# Arduino-on-breadboard.net
KiCad netlist of a schematic drawn in EAGLE
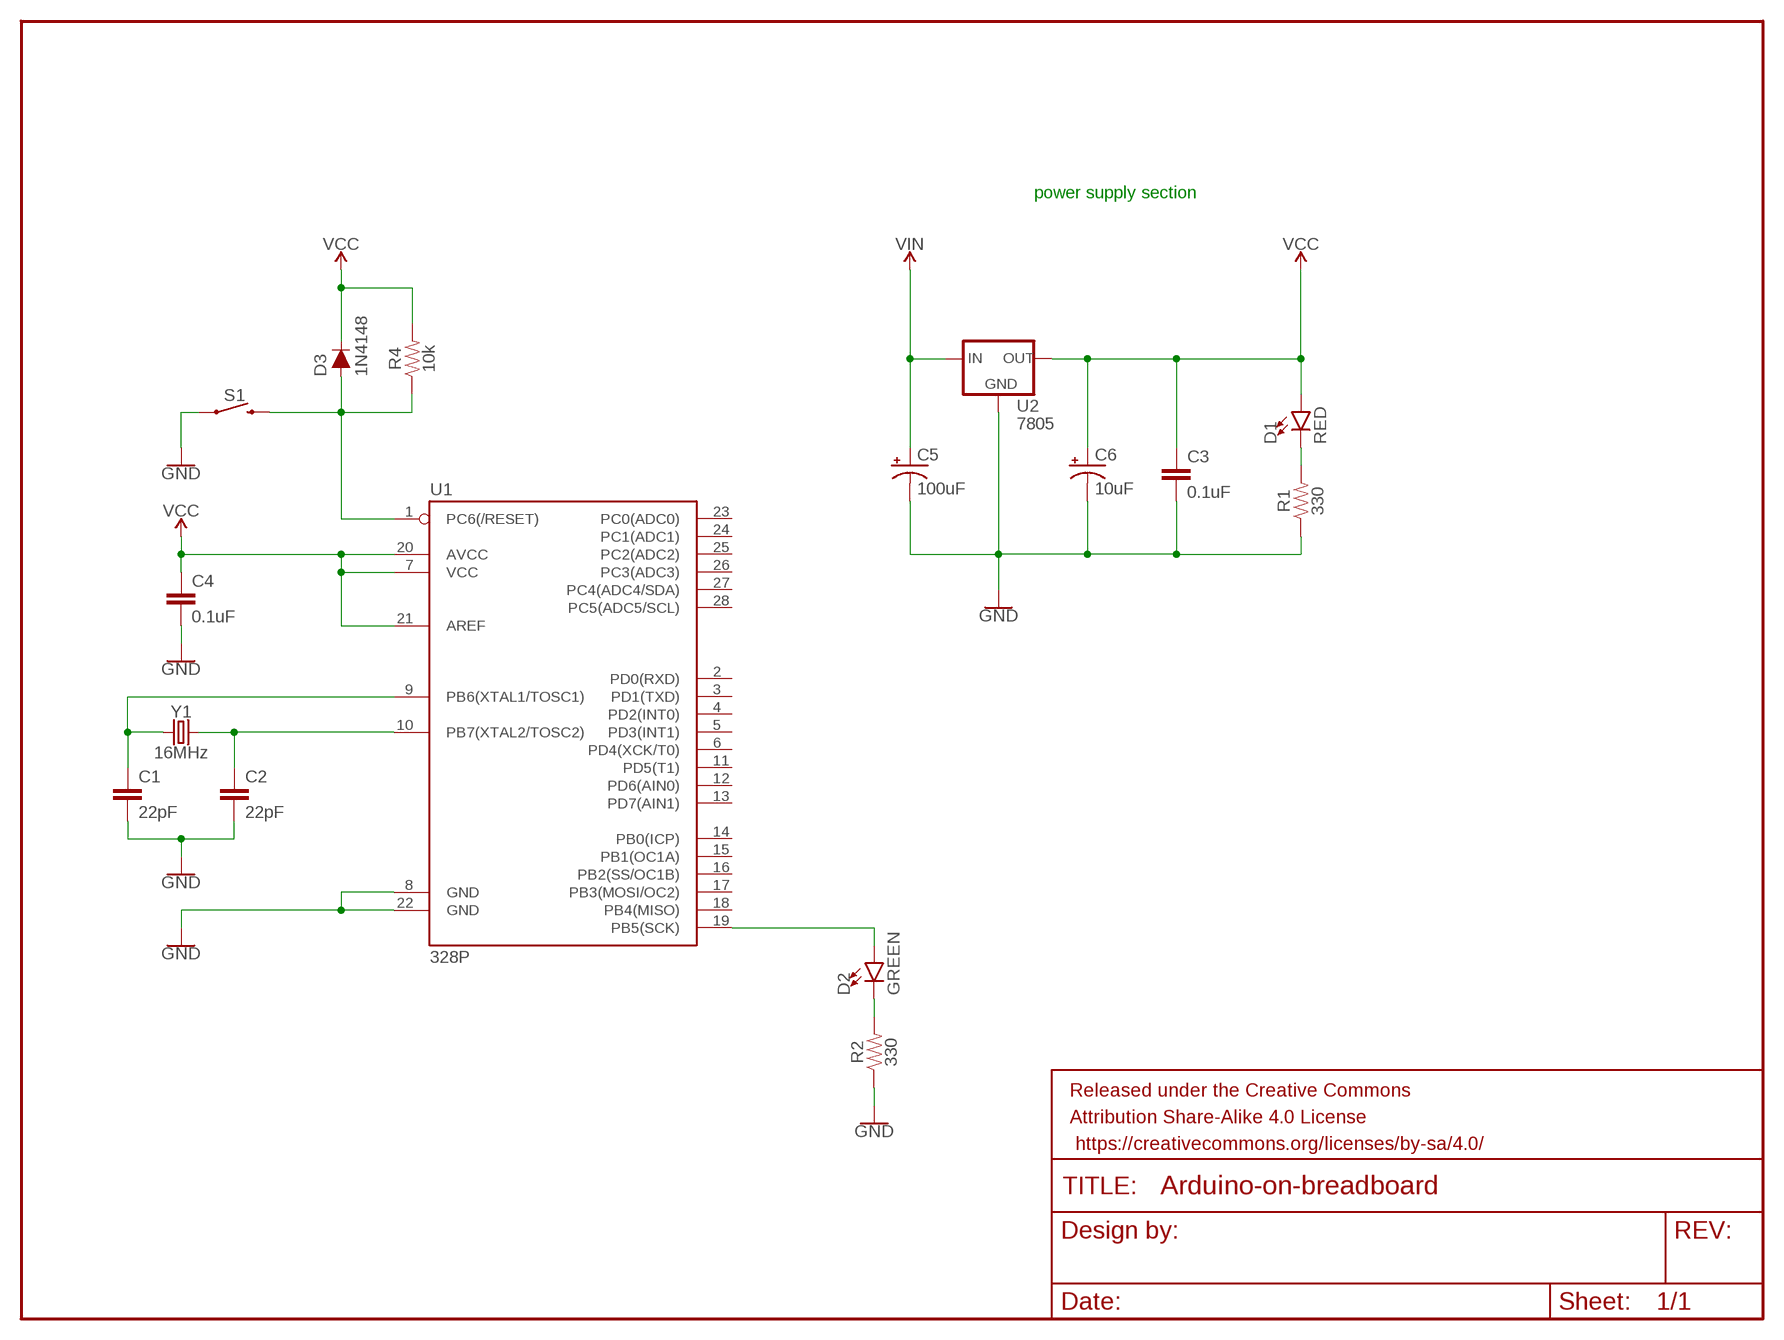
[diagram p0: schematic, sheet 1]

(export (version "E")
  (design (tool "Eeschema 10.0.6"))
  (components
    (comp (ref "C1")
      (value "22pF")
      (footprint "eagle-import:CAP-PTH-2.54")
      (libsource (lib "eagle-import") (part "22PF-PTH-2.54MM-200V-5%"))
    )
    (comp (ref "C2")
      (value "22pF")
      (footprint "eagle-import:CAP-PTH-2.54")
      (libsource (lib "eagle-import") (part "22PF-PTH-2.54MM-200V-5%"))
    )
    (comp (ref "C3")
      (value "0.1uF")
      (footprint "eagle-import:CAP-PTH-SMALL-KIT")
      (libsource (lib "eagle-import") (part "0.1UF-KIT-EZ-50V-20%"))
    )
    (comp (ref "C4")
      (value "0.1uF")
      (footprint "eagle-import:CAP-PTH-SMALL-KIT")
      (libsource (lib "eagle-import") (part "0.1UF-KIT-EZ-50V-20%"))
    )
    (comp (ref "C5")
      (value "100uF")
      (footprint "eagle-import:CPOL-RADIAL-2.5MM-6.5MM")
      (libsource (lib "eagle-import") (part "100UF-POLAR-RADIAL-2.5MM-25V-20%"))
    )
    (comp (ref "C6")
      (value "10uF")
      (footprint "eagle-import:CPOL-RADIAL-2.5MM-6.5MM")
      (libsource (lib "eagle-import") (part "100UF-POLAR-RADIAL-2.5MM-25V-20%"))
    )
    (comp (ref "D1")
      (value "RED")
      (footprint "eagle-import:LED_5MM")
      (libsource (lib "eagle-import") (part "LED5MM"))
    )
    (comp (ref "D2")
      (value "GREEN")
      (footprint "eagle-import:LED_5MM")
      (libsource (lib "eagle-import") (part "LED5MM"))
    )
    (comp (ref "D3")
      (value "1N4148")
      (footprint "eagle-import:DIODE-1N4148")
      (libsource (lib "eagle-import") (part "DIODE-1N4148"))
    )
    (comp (ref "FRAME1")
      (value "FRAME-LETTER")
      (footprint "eagle-import:CREATIVE_COMMONS")
      (libsource (lib "eagle-import") (part "FRAME-LETTER"))
    )
    (comp (ref "R1")
      (value "330")
      (footprint "eagle-import:AXIAL-0.3")
      (libsource (lib "eagle-import") (part "1KOHM-HORIZ-1/4W-5%"))
    )
    (comp (ref "R2")
      (value "330")
      (footprint "eagle-import:AXIAL-0.3")
      (libsource (lib "eagle-import") (part "1KOHM-HORIZ-1/4W-5%"))
    )
    (comp (ref "R4")
      (value "10k")
      (footprint "eagle-import:AXIAL-0.3")
      (libsource (lib "eagle-import") (part "1KOHM-HORIZ-1/4W-5%"))
    )
    (comp (ref "S1")
      (value "MOMENTARY-SWITCH-SPST-SMD-6.0X3.5MM")
      (footprint "eagle-import:TACTILE_SWITCH_SMD_6.0X3.5MM")
      (libsource (lib "eagle-import") (part "MOMENTARY-SWITCH-SPST-SMD-6.0X3.5MM"))
    )
    (comp (ref "U1")
      (value "328P")
      (footprint "eagle-import:DIP28")
      (libsource (lib "eagle-import") (part "ATMEGA328P_PDIP"))
    )
    (comp (ref "U2")
      (value "7805")
      (footprint "eagle-import:78XXL")
      (libsource (lib "eagle-import") (part "V_REG_78XXSIDE"))
    )
    (comp (ref "Y1")
      (value "16MHz")
      (footprint "eagle-import:HC49US")
      (libsource (lib "eagle-import") (part "CRYSTAL-16MHZPTH-HC49US"))
    )
  )
  (nets
    (net (code "1") (name "GND") (class "Default")
      (node (ref "C1") (pin "2") (pinfunction "2_2") (pintype "passive"))
      (node (ref "C2") (pin "2") (pinfunction "2_2") (pintype "passive"))
      (node (ref "C3") (pin "2") (pinfunction "2_2") (pintype "passive"))
      (node (ref "C4") (pin "2") (pinfunction "2_2") (pintype "passive"))
      (node (ref "C5") (pin "2") (pinfunction "-_2") (pintype "passive"))
      (node (ref "C6") (pin "2") (pinfunction "-_2") (pintype "passive"))
      (node (ref "R1") (pin "P$1") (pinfunction "1_P$1") (pintype "passive"))
      (node (ref "R2") (pin "P$1") (pinfunction "1_P$1") (pintype "passive"))
      (node (ref "S1") (pin "1") (pinfunction "1_1") (pintype "passive"))
      (node (ref "U1") (pin "22") (pinfunction "GND_22") (pintype "bidirectional"))
      (node (ref "U1") (pin "8") (pinfunction "GND_8") (pintype "bidirectional"))
      (node (ref "U2") (pin "GND") (pinfunction "GND_GND") (pintype "input"))
    )
    (net (code "2") (name "Net-(D1-C)") (class "Default")
      (node (ref "D1") (pin "K") (pinfunction "C_K") (pintype "passive"))
      (node (ref "R1") (pin "P$2") (pinfunction "2_P$2") (pintype "passive"))
    )
    (net (code "3") (name "Net-(D2-C)") (class "Default")
      (node (ref "D2") (pin "K") (pinfunction "C_K") (pintype "passive"))
      (node (ref "R2") (pin "P$2") (pinfunction "2_P$2") (pintype "passive"))
    )
    (net (code "4") (name "Net-(R4-1)") (class "Default")
      (node (ref "D3") (pin "A") (pinfunction "A_A") (pintype "passive"))
      (node (ref "R4") (pin "P$1") (pinfunction "1_P$1") (pintype "passive"))
      (node (ref "S1") (pin "2") (pinfunction "2_2") (pintype "passive"))
      (node (ref "U1") (pin "1") (pinfunction "PC6(/RESET)_1") (pintype "bidirectional"))
    )
    (net (code "5") (name "Net-(U1-PB5(SCK))") (class "Default")
      (node (ref "D2") (pin "A") (pinfunction "A_A") (pintype "passive"))
      (node (ref "U1") (pin "19") (pinfunction "PB5(SCK)_19") (pintype "bidirectional"))
    )
    (net (code "6") (name "Net-(U1-PB6(XTAL1{slash}TOSC1))") (class "Default")
      (node (ref "C1") (pin "1") (pinfunction "1_1") (pintype "passive"))
      (node (ref "U1") (pin "9") (pinfunction "PB6(XTAL1/TOSC1)_9") (pintype "bidirectional"))
      (node (ref "Y1") (pin "1") (pinfunction "1_1") (pintype "passive"))
    )
    (net (code "7") (name "Net-(U1-PB7(XTAL2{slash}TOSC2))") (class "Default")
      (node (ref "C2") (pin "1") (pinfunction "1_1") (pintype "passive"))
      (node (ref "U1") (pin "10") (pinfunction "PB7(XTAL2/TOSC2)_10") (pintype "bidirectional"))
      (node (ref "Y1") (pin "2") (pinfunction "2_2") (pintype "passive"))
    )
    (net (code "8") (name "VCC") (class "Default")
      (node (ref "C3") (pin "1") (pinfunction "1_1") (pintype "passive"))
      (node (ref "C4") (pin "1") (pinfunction "1_1") (pintype "passive"))
      (node (ref "C5") (pin "1") (pinfunction "+_1") (pintype "passive"))
      (node (ref "C6") (pin "1") (pinfunction "+_1") (pintype "passive"))
      (node (ref "D1") (pin "A") (pinfunction "A_A") (pintype "passive"))
      (node (ref "D3") (pin "C") (pinfunction "C_C") (pintype "passive"))
      (node (ref "R4") (pin "P$2") (pinfunction "2_P$2") (pintype "passive"))
      (node (ref "U1") (pin "20") (pinfunction "AVCC_20") (pintype "bidirectional"))
      (node (ref "U1") (pin "21") (pinfunction "AREF_21") (pintype "bidirectional"))
      (node (ref "U1") (pin "7") (pinfunction "VCC_7") (pintype "bidirectional"))
      (node (ref "U2") (pin "IN") (pinfunction "IN_IN") (pintype "input"))
      (node (ref "U2") (pin "OUT") (pinfunction "OUT_OUT") (pintype "passive"))
    )
    (net (code "9") (name "unconnected-(U1-PB0(ICP)-Pad14)") (class "Default")
      (node (ref "U1") (pin "14") (pinfunction "PB0(ICP)_14") (pintype "bidirectional"))
    )
    (net (code "10") (name "unconnected-(U1-PB1(OC1A)-Pad15)") (class "Default")
      (node (ref "U1") (pin "15") (pinfunction "PB1(OC1A)_15") (pintype "bidirectional"))
    )
    (net (code "11") (name "unconnected-(U1-PB2(SS{slash}OC1B)-Pad16)") (class "Default")
      (node (ref "U1") (pin "16") (pinfunction "PB2(SS/OC1B)_16") (pintype "bidirectional"))
    )
    (net (code "12") (name "unconnected-(U1-PB3(MOSI{slash}OC2)-Pad17)") (class "Default")
      (node (ref "U1") (pin "17") (pinfunction "PB3(MOSI/OC2)_17") (pintype "bidirectional"))
    )
    (net (code "13") (name "unconnected-(U1-PB4(MISO)-Pad18)") (class "Default")
      (node (ref "U1") (pin "18") (pinfunction "PB4(MISO)_18") (pintype "bidirectional"))
    )
    (net (code "14") (name "unconnected-(U1-PC0(ADC0)-Pad23)") (class "Default")
      (node (ref "U1") (pin "23") (pinfunction "PC0(ADC0)_23") (pintype "bidirectional"))
    )
    (net (code "15") (name "unconnected-(U1-PC1(ADC1)-Pad24)") (class "Default")
      (node (ref "U1") (pin "24") (pinfunction "PC1(ADC1)_24") (pintype "bidirectional"))
    )
    (net (code "16") (name "unconnected-(U1-PC2(ADC2)-Pad25)") (class "Default")
      (node (ref "U1") (pin "25") (pinfunction "PC2(ADC2)_25") (pintype "bidirectional"))
    )
    (net (code "17") (name "unconnected-(U1-PC3(ADC3)-Pad26)") (class "Default")
      (node (ref "U1") (pin "26") (pinfunction "PC3(ADC3)_26") (pintype "bidirectional"))
    )
    (net (code "18") (name "unconnected-(U1-PC4(ADC4{slash}SDA)-Pad27)") (class "Default")
      (node (ref "U1") (pin "27") (pinfunction "PC4(ADC4/SDA)_27") (pintype "bidirectional"))
    )
    (net (code "19") (name "unconnected-(U1-PC5(ADC5{slash}SCL)-Pad28)") (class "Default")
      (node (ref "U1") (pin "28") (pinfunction "PC5(ADC5/SCL)_28") (pintype "bidirectional"))
    )
    (net (code "20") (name "unconnected-(U1-PD0(RXD)-Pad2)") (class "Default")
      (node (ref "U1") (pin "2") (pinfunction "PD0(RXD)_2") (pintype "bidirectional"))
    )
    (net (code "21") (name "unconnected-(U1-PD1(TXD)-Pad3)") (class "Default")
      (node (ref "U1") (pin "3") (pinfunction "PD1(TXD)_3") (pintype "bidirectional"))
    )
    (net (code "22") (name "unconnected-(U1-PD2(INT0)-Pad4)") (class "Default")
      (node (ref "U1") (pin "4") (pinfunction "PD2(INT0)_4") (pintype "bidirectional"))
    )
    (net (code "23") (name "unconnected-(U1-PD3(INT1)-Pad5)") (class "Default")
      (node (ref "U1") (pin "5") (pinfunction "PD3(INT1)_5") (pintype "bidirectional"))
    )
    (net (code "24") (name "unconnected-(U1-PD4(XCK{slash}T0)-Pad6)") (class "Default")
      (node (ref "U1") (pin "6") (pinfunction "PD4(XCK/T0)_6") (pintype "bidirectional"))
    )
    (net (code "25") (name "unconnected-(U1-PD5(T1)-Pad11)") (class "Default")
      (node (ref "U1") (pin "11") (pinfunction "PD5(T1)_11") (pintype "bidirectional"))
    )
    (net (code "26") (name "unconnected-(U1-PD6(AIN0)-Pad12)") (class "Default")
      (node (ref "U1") (pin "12") (pinfunction "PD6(AIN0)_12") (pintype "bidirectional"))
    )
    (net (code "27") (name "unconnected-(U1-PD7(AIN1)-Pad13)") (class "Default")
      (node (ref "U1") (pin "13") (pinfunction "PD7(AIN1)_13") (pintype "bidirectional"))
    )
  )
)
